# PowerManagement.net
KiCad netlist of a schematic drawn in Altium Designer
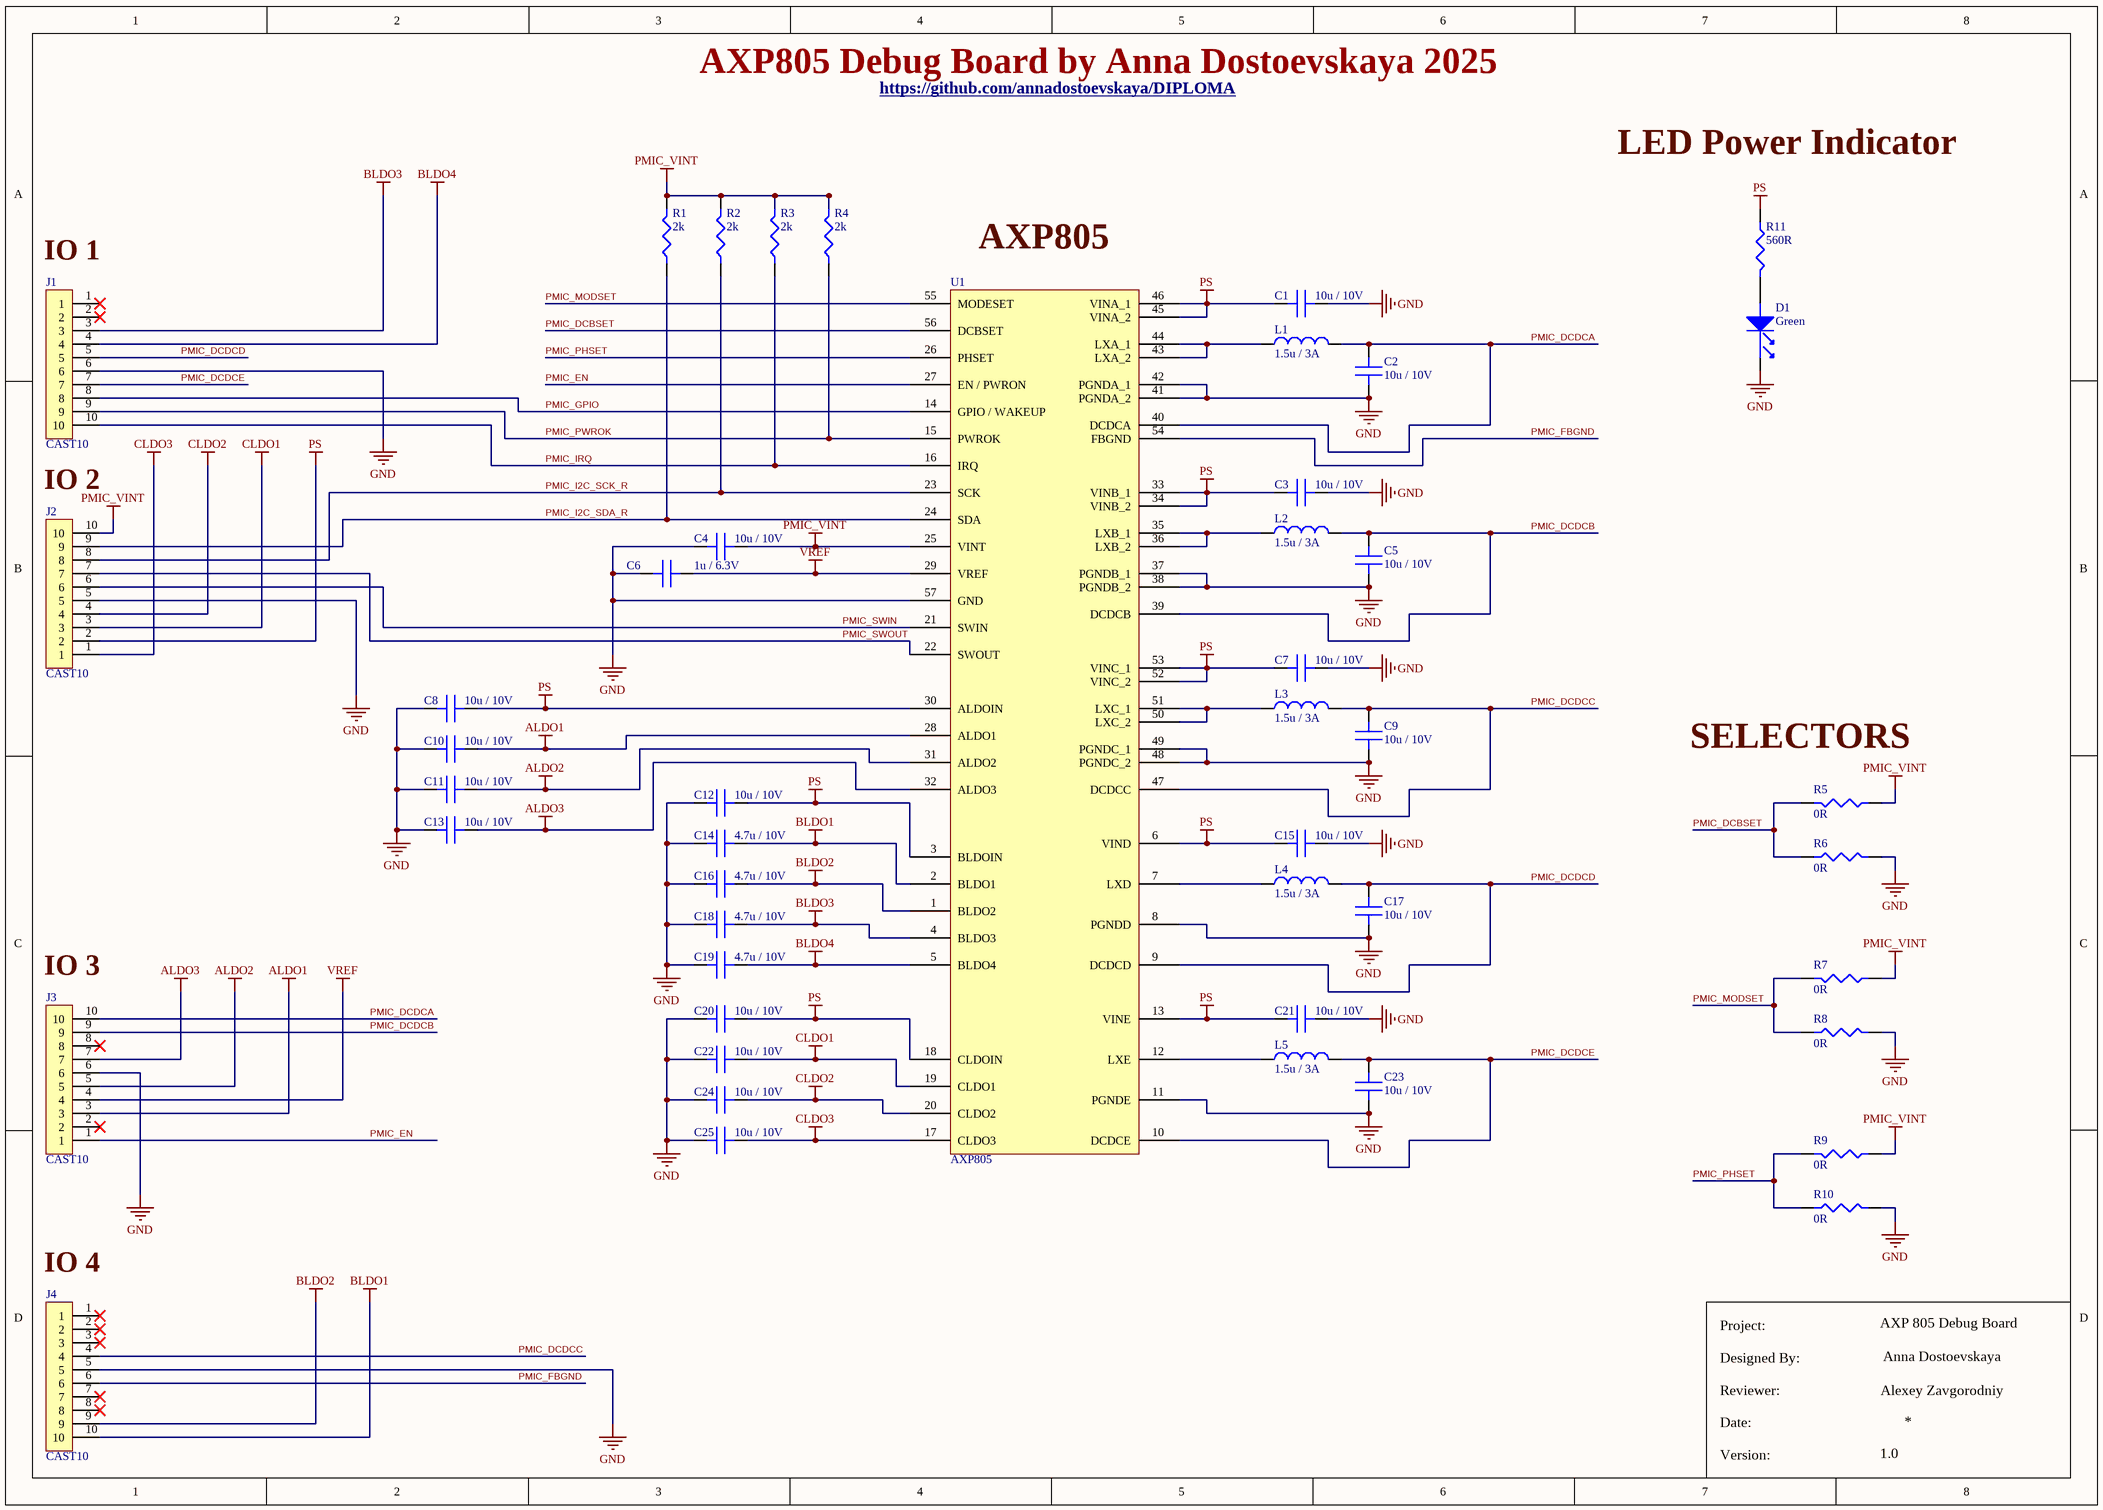
[diagram p0: PowerManagement.SchDoc]

(export (version "E")
  (design (tool "Eeschema 10.0.6"))
  (components
    (comp (ref "C1")
      (value "10u / 10V")
      (footprint "C0603")
      (description "C Series 0603 10 uF 10 V ±10 % Tolerance X5R SMT Multilayer Ceramic Capacitor")
      (fields
        (field (name "MANUFACTURER") "TDK")
        (field (name "MANUFACTURER PART NUMBER") "C1608X5R1A106K080AC")
      )
      (libsource (lib "PowerManagement") (part "C1608X5R1A106K080AC"))
    )
    (comp (ref "C2")
      (value "10u / 10V")
      (footprint "C0603")
      (description "C Series 0603 10 uF 10 V ±10 % Tolerance X5R SMT Multilayer Ceramic Capacitor")
      (fields
        (field (name "MANUFACTURER") "TDK")
        (field (name "MANUFACTURER PART NUMBER") "C1608X5R1A106K080AC")
      )
      (libsource (lib "PowerManagement") (part "C1608X5R1A106K080AC"))
    )
    (comp (ref "C3")
      (value "10u / 10V")
      (footprint "C0603")
      (description "C Series 0603 10 uF 10 V ±10 % Tolerance X5R SMT Multilayer Ceramic Capacitor")
      (fields
        (field (name "MANUFACTURER") "TDK")
        (field (name "MANUFACTURER PART NUMBER") "C1608X5R1A106K080AC")
      )
      (libsource (lib "PowerManagement") (part "C1608X5R1A106K080AC"))
    )
    (comp (ref "C4")
      (value "10u / 10V")
      (footprint "C0603")
      (description "C Series 0603 10 uF 10 V ±10 % Tolerance X5R SMT Multilayer Ceramic Capacitor")
      (fields
        (field (name "MANUFACTURER") "TDK")
        (field (name "MANUFACTURER PART NUMBER") "C1608X5R1A106K080AC")
      )
      (libsource (lib "PowerManagement") (part "C1608X5R1A106K080AC"))
    )
    (comp (ref "C5")
      (value "10u / 10V")
      (footprint "C0603")
      (description "C Series 0603 10 uF 10 V ±10 % Tolerance X5R SMT Multilayer Ceramic Capacitor")
      (fields
        (field (name "MANUFACTURER") "TDK")
        (field (name "MANUFACTURER PART NUMBER") "C1608X5R1A106K080AC")
      )
      (libsource (lib "PowerManagement") (part "C1608X5R1A106K080AC"))
    )
    (comp (ref "C6")
      (value "1u / 6.3V")
      (footprint "C0402")
      (description "Multilayer Ceramic Capacitor, 1 uF, 100 V, ï¿½ 10%, X7R, 0402 [1005 Metric]")
      (fields
        (field (name "MANUFACTURER") "Yageo")
        (field (name "MANUFACTURER PART NUMBER") "CC0402KRX5R5BB105")
      )
      (libsource (lib "PowerManagement") (part "CC0402KRX5R5BB105"))
    )
    (comp (ref "C7")
      (value "10u / 10V")
      (footprint "C0603")
      (description "C Series 0603 10 uF 10 V ±10 % Tolerance X5R SMT Multilayer Ceramic Capacitor")
      (fields
        (field (name "MANUFACTURER") "TDK")
        (field (name "MANUFACTURER PART NUMBER") "C1608X5R1A106K080AC")
      )
      (libsource (lib "PowerManagement") (part "C1608X5R1A106K080AC"))
    )
    (comp (ref "C8")
      (value "10u / 10V")
      (footprint "C0603")
      (description "C Series 0603 10 uF 10 V ±10 % Tolerance X5R SMT Multilayer Ceramic Capacitor")
      (fields
        (field (name "MANUFACTURER") "TDK")
        (field (name "MANUFACTURER PART NUMBER") "C1608X5R1A106K080AC")
      )
      (libsource (lib "PowerManagement") (part "C1608X5R1A106K080AC"))
    )
    (comp (ref "C9")
      (value "10u / 10V")
      (footprint "C0603")
      (description "C Series 0603 10 uF 10 V ±10 % Tolerance X5R SMT Multilayer Ceramic Capacitor")
      (fields
        (field (name "MANUFACTURER") "TDK")
        (field (name "MANUFACTURER PART NUMBER") "C1608X5R1A106K080AC")
      )
      (libsource (lib "PowerManagement") (part "C1608X5R1A106K080AC"))
    )
    (comp (ref "C10")
      (value "10u / 10V")
      (footprint "C0603")
      (description "C Series 0603 10 uF 10 V ±10 % Tolerance X5R SMT Multilayer Ceramic Capacitor")
      (fields
        (field (name "MANUFACTURER") "TDK")
        (field (name "MANUFACTURER PART NUMBER") "C1608X5R1A106K080AC")
      )
      (libsource (lib "PowerManagement") (part "C1608X5R1A106K080AC"))
    )
    (comp (ref "C11")
      (value "10u / 10V")
      (footprint "C0603")
      (description "C Series 0603 10 uF 10 V ±10 % Tolerance X5R SMT Multilayer Ceramic Capacitor")
      (fields
        (field (name "MANUFACTURER") "TDK")
        (field (name "MANUFACTURER PART NUMBER") "C1608X5R1A106K080AC")
      )
      (libsource (lib "PowerManagement") (part "C1608X5R1A106K080AC"))
    )
    (comp (ref "C12")
      (value "10u / 10V")
      (footprint "C0603")
      (description "C Series 0603 10 uF 10 V ±10 % Tolerance X5R SMT Multilayer Ceramic Capacitor")
      (fields
        (field (name "MANUFACTURER") "TDK")
        (field (name "MANUFACTURER PART NUMBER") "C1608X5R1A106K080AC")
      )
      (libsource (lib "PowerManagement") (part "C1608X5R1A106K080AC"))
    )
    (comp (ref "C13")
      (value "10u / 10V")
      (footprint "C0603")
      (description "C Series 0603 10 uF 10 V ±10 % Tolerance X5R SMT Multilayer Ceramic Capacitor")
      (fields
        (field (name "MANUFACTURER") "TDK")
        (field (name "MANUFACTURER PART NUMBER") "C1608X5R1A106K080AC")
      )
      (libsource (lib "PowerManagement") (part "C1608X5R1A106K080AC"))
    )
    (comp (ref "C14")
      (value "4.7u / 10V")
      (footprint "C0603")
      (description "C Series 0603 4.7 uF 10 V ±10 %Tolerance X5R SMT Multilayer Ceramic Capacitor")
      (fields
        (field (name "MANUFACTURER") "TDK")
        (field (name "MANUFACTURER PART NUMBER") "C1608X5R1A475K080AE")
      )
      (libsource (lib "PowerManagement") (part "C1608X5R1A475K080AE"))
    )
    (comp (ref "C15")
      (value "10u / 10V")
      (footprint "C0603")
      (description "C Series 0603 10 uF 10 V ±10 % Tolerance X5R SMT Multilayer Ceramic Capacitor")
      (fields
        (field (name "MANUFACTURER") "TDK")
        (field (name "MANUFACTURER PART NUMBER") "C1608X5R1A106K080AC")
      )
      (libsource (lib "PowerManagement") (part "C1608X5R1A106K080AC"))
    )
    (comp (ref "C16")
      (value "4.7u / 10V")
      (footprint "C0603")
      (description "C Series 0603 4.7 uF 10 V ±10 %Tolerance X5R SMT Multilayer Ceramic Capacitor")
      (fields
        (field (name "MANUFACTURER") "TDK")
        (field (name "MANUFACTURER PART NUMBER") "C1608X5R1A475K080AE")
      )
      (libsource (lib "PowerManagement") (part "C1608X5R1A475K080AE"))
    )
    (comp (ref "C17")
      (value "10u / 10V")
      (footprint "C0603")
      (description "C Series 0603 10 uF 10 V ±10 % Tolerance X5R SMT Multilayer Ceramic Capacitor")
      (fields
        (field (name "MANUFACTURER") "TDK")
        (field (name "MANUFACTURER PART NUMBER") "C1608X5R1A106K080AC")
      )
      (libsource (lib "PowerManagement") (part "C1608X5R1A106K080AC"))
    )
    (comp (ref "C18")
      (value "4.7u / 10V")
      (footprint "C0603")
      (description "C Series 0603 4.7 uF 10 V ±10 %Tolerance X5R SMT Multilayer Ceramic Capacitor")
      (fields
        (field (name "MANUFACTURER") "TDK")
        (field (name "MANUFACTURER PART NUMBER") "C1608X5R1A475K080AE")
      )
      (libsource (lib "PowerManagement") (part "C1608X5R1A475K080AE"))
    )
    (comp (ref "C19")
      (value "4.7u / 10V")
      (footprint "C0603")
      (description "C Series 0603 4.7 uF 10 V ±10 %Tolerance X5R SMT Multilayer Ceramic Capacitor")
      (fields
        (field (name "MANUFACTURER") "TDK")
        (field (name "MANUFACTURER PART NUMBER") "C1608X5R1A475K080AE")
      )
      (libsource (lib "PowerManagement") (part "C1608X5R1A475K080AE"))
    )
    (comp (ref "C20")
      (value "10u / 10V")
      (footprint "C0603")
      (description "C Series 0603 10 uF 10 V ±10 % Tolerance X5R SMT Multilayer Ceramic Capacitor")
      (fields
        (field (name "MANUFACTURER") "TDK")
        (field (name "MANUFACTURER PART NUMBER") "C1608X5R1A106K080AC")
      )
      (libsource (lib "PowerManagement") (part "C1608X5R1A106K080AC"))
    )
    (comp (ref "C21")
      (value "10u / 10V")
      (footprint "C0603")
      (description "C Series 0603 10 uF 10 V ±10 % Tolerance X5R SMT Multilayer Ceramic Capacitor")
      (fields
        (field (name "MANUFACTURER") "TDK")
        (field (name "MANUFACTURER PART NUMBER") "C1608X5R1A106K080AC")
      )
      (libsource (lib "PowerManagement") (part "C1608X5R1A106K080AC"))
    )
    (comp (ref "C22")
      (value "10u / 10V")
      (footprint "C0603")
      (description "C Series 0603 10 uF 10 V ±10 % Tolerance X5R SMT Multilayer Ceramic Capacitor")
      (fields
        (field (name "MANUFACTURER") "TDK")
        (field (name "MANUFACTURER PART NUMBER") "C1608X5R1A106K080AC")
      )
      (libsource (lib "PowerManagement") (part "C1608X5R1A106K080AC"))
    )
    (comp (ref "C23")
      (value "10u / 10V")
      (footprint "C0603")
      (description "C Series 0603 10 uF 10 V ±10 % Tolerance X5R SMT Multilayer Ceramic Capacitor")
      (fields
        (field (name "MANUFACTURER") "TDK")
        (field (name "MANUFACTURER PART NUMBER") "C1608X5R1A106K080AC")
      )
      (libsource (lib "PowerManagement") (part "C1608X5R1A106K080AC"))
    )
    (comp (ref "C24")
      (value "10u / 10V")
      (footprint "C0603")
      (description "C Series 0603 10 uF 10 V ±10 % Tolerance X5R SMT Multilayer Ceramic Capacitor")
      (fields
        (field (name "MANUFACTURER") "TDK")
        (field (name "MANUFACTURER PART NUMBER") "C1608X5R1A106K080AC")
      )
      (libsource (lib "PowerManagement") (part "C1608X5R1A106K080AC"))
    )
    (comp (ref "C25")
      (value "10u / 10V")
      (footprint "C0603")
      (description "C Series 0603 10 uF 10 V ±10 % Tolerance X5R SMT Multilayer Ceramic Capacitor")
      (fields
        (field (name "MANUFACTURER") "TDK")
        (field (name "MANUFACTURER PART NUMBER") "C1608X5R1A106K080AC")
      )
      (libsource (lib "PowerManagement") (part "C1608X5R1A106K080AC"))
    )
    (comp (ref "D1")
      (value "Green")
      (footprint "LED_0603")
      (description "Led Green Diffused 0603 SMD")
      (fields
        (field (name "MANUFACTURER") "Osram Opto")
        (field (name "MANUFACTURER PART NUMBER") "KG EELP41.22-PHRH-35-A8J8-20-R18")
      )
      (libsource (lib "PowerManagement") (part "KG EELP41.22-PHRH-35-A8J8-20-R18"))
    )
    (comp (ref "J1")
      (value "CAST10")
      (footprint "CAST10_2.54MM")
      (description "10x Castellated Plated Through-Holes, 2.54mm Pitch.")
      (libsource (lib "PowerManagement") (part "CAST10_2.54MM"))
    )
    (comp (ref "J2")
      (value "CAST10")
      (footprint "CAST10_2.54MM")
      (description "10x Castellated Plated Through-Holes, 2.54mm Pitch.")
      (libsource (lib "") (part "CAST10_2.54MM_1"))
    )
    (comp (ref "J3")
      (value "CAST10")
      (footprint "CAST10_2.54MM")
      (description "10x Castellated Plated Through-Holes, 2.54mm Pitch.")
      (libsource (lib "") (part "CAST10_2.54MM_1"))
    )
    (comp (ref "J4")
      (value "CAST10")
      (footprint "CAST10_2.54MM")
      (description "10x Castellated Plated Through-Holes, 2.54mm Pitch.")
      (libsource (lib "PowerManagement") (part "CAST10_2.54MM"))
    )
    (comp (ref "L1")
      (value "1.5u / 3A")
      (footprint "SPM3015")
      (description "Inductor Power Shielded Wirewound 1.5uH 20% 100KHz Metal 3.3A 0.0624Ohm DCR T/R")
      (fields
        (field (name "MANUFACTURER") "TDK")
        (field (name "MANUFACTURER PART NUMBER") "SPM3015T-1R5M-LR")
      )
      (libsource (lib "PowerManagement") (part "SPM3015T-1R5M-LR"))
    )
    (comp (ref "L2")
      (value "1.5u / 3A")
      (footprint "SPM3015")
      (description "Inductor Power Shielded Wirewound 1.5uH 20% 100KHz Metal 3.3A 0.0624Ohm DCR T/R")
      (fields
        (field (name "MANUFACTURER") "TDK")
        (field (name "MANUFACTURER PART NUMBER") "SPM3015T-1R5M-LR")
      )
      (libsource (lib "PowerManagement") (part "SPM3015T-1R5M-LR"))
    )
    (comp (ref "L3")
      (value "1.5u / 3A")
      (footprint "SPM3015")
      (description "Inductor Power Shielded Wirewound 1.5uH 20% 100KHz Metal 3.3A 0.0624Ohm DCR T/R")
      (fields
        (field (name "MANUFACTURER") "TDK")
        (field (name "MANUFACTURER PART NUMBER") "SPM3015T-1R5M-LR")
      )
      (libsource (lib "PowerManagement") (part "SPM3015T-1R5M-LR"))
    )
    (comp (ref "L4")
      (value "1.5u / 3A")
      (footprint "SPM3015")
      (description "Inductor Power Shielded Wirewound 1.5uH 20% 100KHz Metal 3.3A 0.0624Ohm DCR T/R")
      (fields
        (field (name "MANUFACTURER") "TDK")
        (field (name "MANUFACTURER PART NUMBER") "SPM3015T-1R5M-LR")
      )
      (libsource (lib "PowerManagement") (part "SPM3015T-1R5M-LR"))
    )
    (comp (ref "L5")
      (value "1.5u / 3A")
      (footprint "SPM3015")
      (description "Inductor Power Shielded Wirewound 1.5uH 20% 100KHz Metal 3.3A 0.0624Ohm DCR T/R")
      (fields
        (field (name "MANUFACTURER") "TDK")
        (field (name "MANUFACTURER PART NUMBER") "SPM3015T-1R5M-LR")
      )
      (libsource (lib "PowerManagement") (part "SPM3015T-1R5M-LR"))
    )
    (comp (ref "R1")
      (value "2k")
      (footprint "R0402")
      (description "General Purpose Chip Resistor Thick Film 0402 2kOhm 0.1% Paper T/R")
      (fields
        (field (name "MANUFACTURER") "Yageo")
        (field (name "MANUFACTURER PART NUMBER") "RC0402BR-072KL")
      )
      (libsource (lib "PowerManagement") (part "RC0402BR-072KL"))
    )
    (comp (ref "R2")
      (value "2k")
      (footprint "R0402")
      (description "General Purpose Chip Resistor Thick Film 0402 2kOhm 0.1% Paper T/R")
      (fields
        (field (name "MANUFACTURER") "Yageo")
        (field (name "MANUFACTURER PART NUMBER") "RC0402BR-072KL")
      )
      (libsource (lib "PowerManagement") (part "RC0402BR-072KL"))
    )
    (comp (ref "R3")
      (value "2k")
      (footprint "R0402")
      (description "General Purpose Chip Resistor Thick Film 0402 2kOhm 0.1% Paper T/R")
      (fields
        (field (name "MANUFACTURER") "Yageo")
        (field (name "MANUFACTURER PART NUMBER") "RC0402BR-072KL")
      )
      (libsource (lib "PowerManagement") (part "RC0402BR-072KL"))
    )
    (comp (ref "R4")
      (value "2k")
      (footprint "R0402")
      (description "General Purpose Chip Resistor Thick Film 0402 2kOhm 0.1% Paper T/R")
      (fields
        (field (name "MANUFACTURER") "Yageo")
        (field (name "MANUFACTURER PART NUMBER") "RC0402BR-072KL")
      )
      (libsource (lib "PowerManagement") (part "RC0402BR-072KL"))
    )
    (comp (ref "R5")
      (value "0R")
      (footprint "R0402")
      (description "Zero Ohm Resistor, Jumper, 0402 [1005 Metric], Metal Film, 63 mW, 11 A, Surface Mount")
      (fields
        (field (name "MANUFACTURER") "Yageo")
        (field (name "MANUFACTURER PART NUMBER") "PA0402-R-070RL")
      )
      (libsource (lib "PowerManagement") (part "PA0402-R-070RL"))
    )
    (comp (ref "R6")
      (value "0R")
      (footprint "R0402")
      (description "Zero Ohm Resistor, Jumper, 0402 [1005 Metric], Metal Film, 63 mW, 11 A, Surface Mount")
      (fields
        (field (name "MANUFACTURER") "Yageo")
        (field (name "MANUFACTURER PART NUMBER") "PA0402-R-070RL")
      )
      (libsource (lib "PowerManagement") (part "PA0402-R-070RL"))
    )
    (comp (ref "R7")
      (value "0R")
      (footprint "R0402")
      (description "Zero Ohm Resistor, Jumper, 0402 [1005 Metric], Metal Film, 63 mW, 11 A, Surface Mount")
      (fields
        (field (name "MANUFACTURER") "Yageo")
        (field (name "MANUFACTURER PART NUMBER") "PA0402-R-070RL")
      )
      (libsource (lib "PowerManagement") (part "PA0402-R-070RL"))
    )
    (comp (ref "R8")
      (value "0R")
      (footprint "R0402")
      (description "Zero Ohm Resistor, Jumper, 0402 [1005 Metric], Metal Film, 63 mW, 11 A, Surface Mount")
      (fields
        (field (name "MANUFACTURER") "Yageo")
        (field (name "MANUFACTURER PART NUMBER") "PA0402-R-070RL")
      )
      (libsource (lib "PowerManagement") (part "PA0402-R-070RL"))
    )
    (comp (ref "R9")
      (value "0R")
      (footprint "R0402")
      (description "Zero Ohm Resistor, Jumper, 0402 [1005 Metric], Metal Film, 63 mW, 11 A, Surface Mount")
      (fields
        (field (name "MANUFACTURER") "Yageo")
        (field (name "MANUFACTURER PART NUMBER") "PA0402-R-070RL")
      )
      (libsource (lib "PowerManagement") (part "PA0402-R-070RL"))
    )
    (comp (ref "R10")
      (value "0R")
      (footprint "R0402")
      (description "Zero Ohm Resistor, Jumper, 0402 [1005 Metric], Metal Film, 63 mW, 11 A, Surface Mount")
      (fields
        (field (name "MANUFACTURER") "Yageo")
        (field (name "MANUFACTURER PART NUMBER") "PA0402-R-070RL")
      )
      (libsource (lib "PowerManagement") (part "PA0402-R-070RL"))
    )
    (comp (ref "R11")
      (value "560R")
      (footprint "R0402")
      (description "SMD Chip Resistor, 560 Ohm, ± 1%, 63 mW, 0402 [1005 Metric], Thick Film, General Purpose")
      (fields
        (field (name "MANUFACTURER") "Yageo")
        (field (name "MANUFACTURER PART NUMBER") "RC0402FR-13560RL")
      )
      (libsource (lib "PowerManagement") (part "RC0402FR-13560RL"))
    )
    (comp (ref "U1")
      (value "AXP805")
      (footprint "QFN7x7MM")
      (description "PMIC for Multi-Core High-Performance System")
      (fields (field (name "MANUFACTURER") "X-Powers"))
      (libsource (lib "PowerManagement") (part "AXP805"))
    )
  )
  (nets
    (net (code "1") (name "/PMIC_DCBSET") (class "Default")
      (node (ref "R5") (pin "2") (pinfunction "2_2") (pintype "passive"))
      (node (ref "R6") (pin "1") (pinfunction "1_1") (pintype "passive"))
      (node (ref "U1") (pin "56") (pinfunction "DCBSET_56") (pintype "passive"))
    )
    (net (code "2") (name "/PMIC_DCDCA") (class "Default")
      (node (ref "C2") (pin "2") (pinfunction "2_2") (pintype "passive"))
      (node (ref "J3") (pin "10") (pinfunction "10_10") (pintype "passive"))
      (node (ref "L1") (pin "2") (pinfunction "2_2") (pintype "passive"))
      (node (ref "U1") (pin "40") (pinfunction "DCDCA_40") (pintype "passive"))
    )
    (net (code "3") (name "/PMIC_DCDCB") (class "Default")
      (node (ref "C5") (pin "2") (pinfunction "2_2") (pintype "passive"))
      (node (ref "J3") (pin "9") (pinfunction "9_9") (pintype "passive"))
      (node (ref "L2") (pin "2") (pinfunction "2_2") (pintype "passive"))
      (node (ref "U1") (pin "39") (pinfunction "DCDCB_39") (pintype "passive"))
    )
    (net (code "4") (name "/PMIC_DCDCC") (class "Default")
      (node (ref "C9") (pin "2") (pinfunction "2_2") (pintype "passive"))
      (node (ref "J4") (pin "4") (pinfunction "4_4") (pintype "passive"))
      (node (ref "L3") (pin "2") (pinfunction "2_2") (pintype "passive"))
      (node (ref "U1") (pin "47") (pinfunction "DCDCC_47") (pintype "passive"))
    )
    (net (code "5") (name "/PMIC_DCDCD") (class "Default")
      (node (ref "C17") (pin "2") (pinfunction "2_2") (pintype "passive"))
      (node (ref "J1") (pin "5") (pinfunction "5_5") (pintype "passive"))
      (node (ref "L4") (pin "2") (pinfunction "2_2") (pintype "passive"))
      (node (ref "U1") (pin "9") (pinfunction "DCDCD_9") (pintype "passive"))
    )
    (net (code "6") (name "/PMIC_DCDCE") (class "Default")
      (node (ref "C23") (pin "2") (pinfunction "2_2") (pintype "passive"))
      (node (ref "J1") (pin "7") (pinfunction "7_7") (pintype "passive"))
      (node (ref "L5") (pin "2") (pinfunction "2_2") (pintype "passive"))
      (node (ref "U1") (pin "10") (pinfunction "DCDCE_10") (pintype "passive"))
    )
    (net (code "7") (name "/PMIC_EN") (class "Default")
      (node (ref "J3") (pin "1") (pinfunction "1_1") (pintype "passive"))
      (node (ref "U1") (pin "27") (pinfunction "EN_/_PWRON_27") (pintype "passive"))
    )
    (net (code "8") (name "/PMIC_FBGND") (class "Default")
      (node (ref "J4") (pin "6") (pinfunction "6_6") (pintype "passive"))
      (node (ref "U1") (pin "54") (pinfunction "FBGND_54") (pintype "passive"))
    )
    (net (code "9") (name "/PMIC_GPIO") (class "Default")
      (node (ref "J1") (pin "8") (pinfunction "8_8") (pintype "passive"))
      (node (ref "U1") (pin "14") (pinfunction "GPIO_/_WAKEUP_14") (pintype "passive"))
    )
    (net (code "10") (name "/PMIC_I2C_SCK_R") (class "Default")
      (node (ref "J2") (pin "8") (pinfunction "8_8") (pintype "passive"))
      (node (ref "R2") (pin "1") (pinfunction "1_1") (pintype "passive"))
      (node (ref "U1") (pin "23") (pinfunction "SCK_23") (pintype "passive"))
    )
    (net (code "11") (name "/PMIC_I2C_SDA_R") (class "Default")
      (node (ref "J2") (pin "9") (pinfunction "9_9") (pintype "passive"))
      (node (ref "R1") (pin "1") (pinfunction "1_1") (pintype "passive"))
      (node (ref "U1") (pin "24") (pinfunction "SDA_24") (pintype "passive"))
    )
    (net (code "12") (name "/PMIC_IRQ") (class "Default")
      (node (ref "J1") (pin "10") (pinfunction "10_10") (pintype "passive"))
      (node (ref "R3") (pin "1") (pinfunction "1_1") (pintype "passive"))
      (node (ref "U1") (pin "16") (pinfunction "IRQ_16") (pintype "passive"))
    )
    (net (code "13") (name "/PMIC_MODSET") (class "Default")
      (node (ref "R7") (pin "2") (pinfunction "2_2") (pintype "passive"))
      (node (ref "R8") (pin "1") (pinfunction "1_1") (pintype "passive"))
      (node (ref "U1") (pin "55") (pinfunction "MODESET_55") (pintype "passive"))
    )
    (net (code "14") (name "/PMIC_PHSET") (class "Default")
      (node (ref "R10") (pin "1") (pinfunction "1_1") (pintype "passive"))
      (node (ref "R9") (pin "2") (pinfunction "2_2") (pintype "passive"))
      (node (ref "U1") (pin "26") (pinfunction "PHSET_26") (pintype "passive"))
    )
    (net (code "15") (name "/PMIC_PWROK") (class "Default")
      (node (ref "J1") (pin "9") (pinfunction "9_9") (pintype "passive"))
      (node (ref "R4") (pin "1") (pinfunction "1_1") (pintype "passive"))
      (node (ref "U1") (pin "15") (pinfunction "PWROK_15") (pintype "passive"))
    )
    (net (code "16") (name "/PMIC_SWIN") (class "Default")
      (node (ref "J2") (pin "6") (pinfunction "6_6") (pintype "passive"))
      (node (ref "U1") (pin "21") (pinfunction "SWIN_21") (pintype "passive"))
    )
    (net (code "17") (name "/PMIC_SWOUT") (class "Default")
      (node (ref "J2") (pin "7") (pinfunction "7_7") (pintype "passive"))
      (node (ref "U1") (pin "22") (pinfunction "SWOUT_22") (pintype "passive"))
    )
    (net (code "18") (name "ALDO1") (class "Default")
      (node (ref "C10") (pin "2") (pinfunction "2_2") (pintype "passive"))
      (node (ref "J3") (pin "3") (pinfunction "3_3") (pintype "passive"))
      (node (ref "U1") (pin "28") (pinfunction "ALDO1_28") (pintype "passive"))
    )
    (net (code "19") (name "ALDO2") (class "Default")
      (node (ref "C11") (pin "2") (pinfunction "2_2") (pintype "passive"))
      (node (ref "J3") (pin "5") (pinfunction "5_5") (pintype "passive"))
      (node (ref "U1") (pin "31") (pinfunction "ALDO2_31") (pintype "passive"))
    )
    (net (code "20") (name "ALDO3") (class "Default")
      (node (ref "C13") (pin "2") (pinfunction "2_2") (pintype "passive"))
      (node (ref "J3") (pin "7") (pinfunction "7_7") (pintype "passive"))
      (node (ref "U1") (pin "32") (pinfunction "ALDO3_32") (pintype "passive"))
    )
    (net (code "21") (name "BLDO1") (class "Default")
      (node (ref "C14") (pin "2") (pinfunction "2_2") (pintype "passive"))
      (node (ref "J4") (pin "10") (pinfunction "10_10") (pintype "passive"))
      (node (ref "U1") (pin "2") (pinfunction "BLDO1_2") (pintype "passive"))
    )
    (net (code "22") (name "BLDO2") (class "Default")
      (node (ref "C16") (pin "2") (pinfunction "2_2") (pintype "passive"))
      (node (ref "J4") (pin "9") (pinfunction "9_9") (pintype "passive"))
      (node (ref "U1") (pin "1") (pinfunction "BLDO2_1") (pintype "passive"))
    )
    (net (code "23") (name "BLDO3") (class "Default")
      (node (ref "C18") (pin "2") (pinfunction "2_2") (pintype "passive"))
      (node (ref "J1") (pin "3") (pinfunction "3_3") (pintype "passive"))
      (node (ref "U1") (pin "4") (pinfunction "BLDO3_4") (pintype "passive"))
    )
    (net (code "24") (name "BLDO4") (class "Default")
      (node (ref "C19") (pin "2") (pinfunction "2_2") (pintype "passive"))
      (node (ref "J1") (pin "4") (pinfunction "4_4") (pintype "passive"))
      (node (ref "U1") (pin "5") (pinfunction "BLDO4_5") (pintype "passive"))
    )
    (net (code "25") (name "CLDO1") (class "Default")
      (node (ref "C22") (pin "2") (pinfunction "2_2") (pintype "passive"))
      (node (ref "J2") (pin "3") (pinfunction "3_3") (pintype "passive"))
      (node (ref "U1") (pin "19") (pinfunction "CLDO1_19") (pintype "passive"))
    )
    (net (code "26") (name "CLDO2") (class "Default")
      (node (ref "C24") (pin "2") (pinfunction "2_2") (pintype "passive"))
      (node (ref "J2") (pin "4") (pinfunction "4_4") (pintype "passive"))
      (node (ref "U1") (pin "20") (pinfunction "CLDO2_20") (pintype "passive"))
    )
    (net (code "27") (name "CLDO3") (class "Default")
      (node (ref "C25") (pin "2") (pinfunction "2_2") (pintype "passive"))
      (node (ref "J2") (pin "1") (pinfunction "1_1") (pintype "passive"))
      (node (ref "U1") (pin "17") (pinfunction "CLDO3_17") (pintype "passive"))
    )
    (net (code "28") (name "GND") (class "Default")
      (node (ref "C1") (pin "2") (pinfunction "2_2") (pintype "passive"))
      (node (ref "C10") (pin "1") (pinfunction "1_1") (pintype "passive"))
      (node (ref "C11") (pin "1") (pinfunction "1_1") (pintype "passive"))
      (node (ref "C12") (pin "1") (pinfunction "1_1") (pintype "passive"))
      (node (ref "C13") (pin "1") (pinfunction "1_1") (pintype "passive"))
      (node (ref "C14") (pin "1") (pinfunction "1_1") (pintype "passive"))
      (node (ref "C15") (pin "2") (pinfunction "2_2") (pintype "passive"))
      (node (ref "C16") (pin "1") (pinfunction "1_1") (pintype "passive"))
      (node (ref "C17") (pin "1") (pinfunction "1_1") (pintype "passive"))
      (node (ref "C18") (pin "1") (pinfunction "1_1") (pintype "passive"))
      (node (ref "C19") (pin "1") (pinfunction "1_1") (pintype "passive"))
      (node (ref "C2") (pin "1") (pinfunction "1_1") (pintype "passive"))
      (node (ref "C20") (pin "1") (pinfunction "1_1") (pintype "passive"))
      (node (ref "C21") (pin "2") (pinfunction "2_2") (pintype "passive"))
      (node (ref "C22") (pin "1") (pinfunction "1_1") (pintype "passive"))
      (node (ref "C23") (pin "1") (pinfunction "1_1") (pintype "passive"))
      (node (ref "C24") (pin "1") (pinfunction "1_1") (pintype "passive"))
      (node (ref "C25") (pin "1") (pinfunction "1_1") (pintype "passive"))
      (node (ref "C3") (pin "2") (pinfunction "2_2") (pintype "passive"))
      (node (ref "C4") (pin "1") (pinfunction "1_1") (pintype "passive"))
      (node (ref "C5") (pin "1") (pinfunction "1_1") (pintype "passive"))
      (node (ref "C6") (pin "1") (pinfunction "1_1") (pintype "passive"))
      (node (ref "C7") (pin "2") (pinfunction "2_2") (pintype "passive"))
      (node (ref "C8") (pin "1") (pinfunction "1_1") (pintype "passive"))
      (node (ref "C9") (pin "1") (pinfunction "1_1") (pintype "passive"))
      (node (ref "D1") (pin "1") (pinfunction "Cathode_1") (pintype "passive"))
      (node (ref "J1") (pin "6") (pinfunction "6_6") (pintype "passive"))
      (node (ref "J2") (pin "5") (pinfunction "5_5") (pintype "passive"))
      (node (ref "J3") (pin "6") (pinfunction "6_6") (pintype "passive"))
      (node (ref "J4") (pin "5") (pinfunction "5_5") (pintype "passive"))
      (node (ref "R10") (pin "2") (pinfunction "2_2") (pintype "passive"))
      (node (ref "R6") (pin "2") (pinfunction "2_2") (pintype "passive"))
      (node (ref "R8") (pin "2") (pinfunction "2_2") (pintype "passive"))
      (node (ref "U1") (pin "11") (pinfunction "PGNDE_11") (pintype "passive"))
      (node (ref "U1") (pin "37") (pinfunction "PGNDB_1_37") (pintype "passive"))
      (node (ref "U1") (pin "38") (pinfunction "PGNDB_2_38") (pintype "passive"))
      (node (ref "U1") (pin "41") (pinfunction "PGNDA_2_41") (pintype "passive"))
      (node (ref "U1") (pin "42") (pinfunction "PGNDA_1_42") (pintype "passive"))
      (node (ref "U1") (pin "48") (pinfunction "PGNDC_2_48") (pintype "passive"))
      (node (ref "U1") (pin "49") (pinfunction "PGNDC_1_49") (pintype "passive"))
      (node (ref "U1") (pin "57") (pinfunction "GND_57") (pintype "passive"))
      (node (ref "U1") (pin "8") (pinfunction "PGNDD_8") (pintype "passive"))
    )
    (net (code "29") (name "Net-(D1-Anode)") (class "Default")
      (node (ref "D1") (pin "2") (pinfunction "Anode_2") (pintype "passive"))
      (node (ref "R11") (pin "2") (pinfunction "2_2") (pintype "passive"))
    )
    (net (code "30") (name "Net-(U1-LXA_1)") (class "Default")
      (node (ref "L1") (pin "1") (pinfunction "1_1") (pintype "passive"))
      (node (ref "U1") (pin "43") (pinfunction "LXA_2_43") (pintype "passive"))
      (node (ref "U1") (pin "44") (pinfunction "LXA_1_44") (pintype "passive"))
    )
    (net (code "31") (name "Net-(U1-LXB_1)") (class "Default")
      (node (ref "L2") (pin "1") (pinfunction "1_1") (pintype "passive"))
      (node (ref "U1") (pin "35") (pinfunction "LXB_1_35") (pintype "passive"))
      (node (ref "U1") (pin "36") (pinfunction "LXB_2_36") (pintype "passive"))
    )
    (net (code "32") (name "Net-(U1-LXC_1)") (class "Default")
      (node (ref "L3") (pin "1") (pinfunction "1_1") (pintype "passive"))
      (node (ref "U1") (pin "50") (pinfunction "LXC_2_50") (pintype "passive"))
      (node (ref "U1") (pin "51") (pinfunction "LXC_1_51") (pintype "passive"))
    )
    (net (code "33") (name "Net-(U1-LXD)") (class "Default")
      (node (ref "L4") (pin "1") (pinfunction "1_1") (pintype "passive"))
      (node (ref "U1") (pin "7") (pinfunction "LXD_7") (pintype "passive"))
    )
    (net (code "34") (name "Net-(U1-LXE)") (class "Default")
      (node (ref "L5") (pin "1") (pinfunction "1_1") (pintype "passive"))
      (node (ref "U1") (pin "12") (pinfunction "LXE_12") (pintype "passive"))
    )
    (net (code "35") (name "PMIC_VINT") (class "Default")
      (node (ref "C4") (pin "2") (pinfunction "2_2") (pintype "passive"))
      (node (ref "J2") (pin "10") (pinfunction "10_10") (pintype "passive"))
      (node (ref "R1") (pin "2") (pinfunction "2_2") (pintype "passive"))
      (node (ref "R2") (pin "2") (pinfunction "2_2") (pintype "passive"))
      (node (ref "R3") (pin "2") (pinfunction "2_2") (pintype "passive"))
      (node (ref "R4") (pin "2") (pinfunction "2_2") (pintype "passive"))
      (node (ref "R5") (pin "1") (pinfunction "1_1") (pintype "passive"))
      (node (ref "R7") (pin "1") (pinfunction "1_1") (pintype "passive"))
      (node (ref "R9") (pin "1") (pinfunction "1_1") (pintype "passive"))
      (node (ref "U1") (pin "25") (pinfunction "VINT_25") (pintype "passive"))
    )
    (net (code "36") (name "PS") (class "Default")
      (node (ref "C1") (pin "1") (pinfunction "1_1") (pintype "passive"))
      (node (ref "C12") (pin "2") (pinfunction "2_2") (pintype "passive"))
      (node (ref "C15") (pin "1") (pinfunction "1_1") (pintype "passive"))
      (node (ref "C20") (pin "2") (pinfunction "2_2") (pintype "passive"))
      (node (ref "C21") (pin "1") (pinfunction "1_1") (pintype "passive"))
      (node (ref "C3") (pin "1") (pinfunction "1_1") (pintype "passive"))
      (node (ref "C7") (pin "1") (pinfunction "1_1") (pintype "passive"))
      (node (ref "C8") (pin "2") (pinfunction "2_2") (pintype "passive"))
      (node (ref "J2") (pin "2") (pinfunction "2_2") (pintype "passive"))
      (node (ref "R11") (pin "1") (pinfunction "1_1") (pintype "passive"))
      (node (ref "U1") (pin "13") (pinfunction "VINE_13") (pintype "passive"))
      (node (ref "U1") (pin "18") (pinfunction "CLDOIN_18") (pintype "passive"))
      (node (ref "U1") (pin "3") (pinfunction "BLDOIN_3") (pintype "passive"))
      (node (ref "U1") (pin "30") (pinfunction "ALDOIN_30") (pintype "passive"))
      (node (ref "U1") (pin "33") (pinfunction "VINB_1_33") (pintype "passive"))
      (node (ref "U1") (pin "34") (pinfunction "VINB_2_34") (pintype "passive"))
      (node (ref "U1") (pin "45") (pinfunction "VINA_2_45") (pintype "passive"))
      (node (ref "U1") (pin "46") (pinfunction "VINA_1_46") (pintype "passive"))
      (node (ref "U1") (pin "52") (pinfunction "VINC_2_52") (pintype "passive"))
      (node (ref "U1") (pin "53") (pinfunction "VINC_1_53") (pintype "passive"))
      (node (ref "U1") (pin "6") (pinfunction "VIND_6") (pintype "passive"))
    )
    (net (code "37") (name "VREF") (class "Default")
      (node (ref "C6") (pin "2") (pinfunction "2_2") (pintype "passive"))
      (node (ref "J3") (pin "4") (pinfunction "4_4") (pintype "passive"))
      (node (ref "U1") (pin "29") (pinfunction "VREF_29") (pintype "passive"))
    )
    (net (code "38") (name "unconnected-(J1-Pad1)") (class "Default")
      (node (ref "J1") (pin "1") (pinfunction "1_1") (pintype "passive+no_connect"))
    )
    (net (code "39") (name "unconnected-(J1-Pad2)") (class "Default")
      (node (ref "J1") (pin "2") (pinfunction "2_2") (pintype "passive+no_connect"))
    )
    (net (code "40") (name "unconnected-(J3-Pad2)") (class "Default")
      (node (ref "J3") (pin "2") (pinfunction "2_2") (pintype "passive+no_connect"))
    )
    (net (code "41") (name "unconnected-(J3-Pad8)") (class "Default")
      (node (ref "J3") (pin "8") (pinfunction "8_8") (pintype "passive+no_connect"))
    )
    (net (code "42") (name "unconnected-(J4-Pad1)") (class "Default")
      (node (ref "J4") (pin "1") (pinfunction "1_1") (pintype "passive+no_connect"))
    )
    (net (code "43") (name "unconnected-(J4-Pad2)") (class "Default")
      (node (ref "J4") (pin "2") (pinfunction "2_2") (pintype "passive+no_connect"))
    )
    (net (code "44") (name "unconnected-(J4-Pad3)") (class "Default")
      (node (ref "J4") (pin "3") (pinfunction "3_3") (pintype "passive+no_connect"))
    )
    (net (code "45") (name "unconnected-(J4-Pad7)") (class "Default")
      (node (ref "J4") (pin "7") (pinfunction "7_7") (pintype "passive+no_connect"))
    )
    (net (code "46") (name "unconnected-(J4-Pad8)") (class "Default")
      (node (ref "J4") (pin "8") (pinfunction "8_8") (pintype "passive+no_connect"))
    )
  )
)
